# CW313_Power_Supplies.net
KiCad netlist of a schematic drawn in Altium Designer
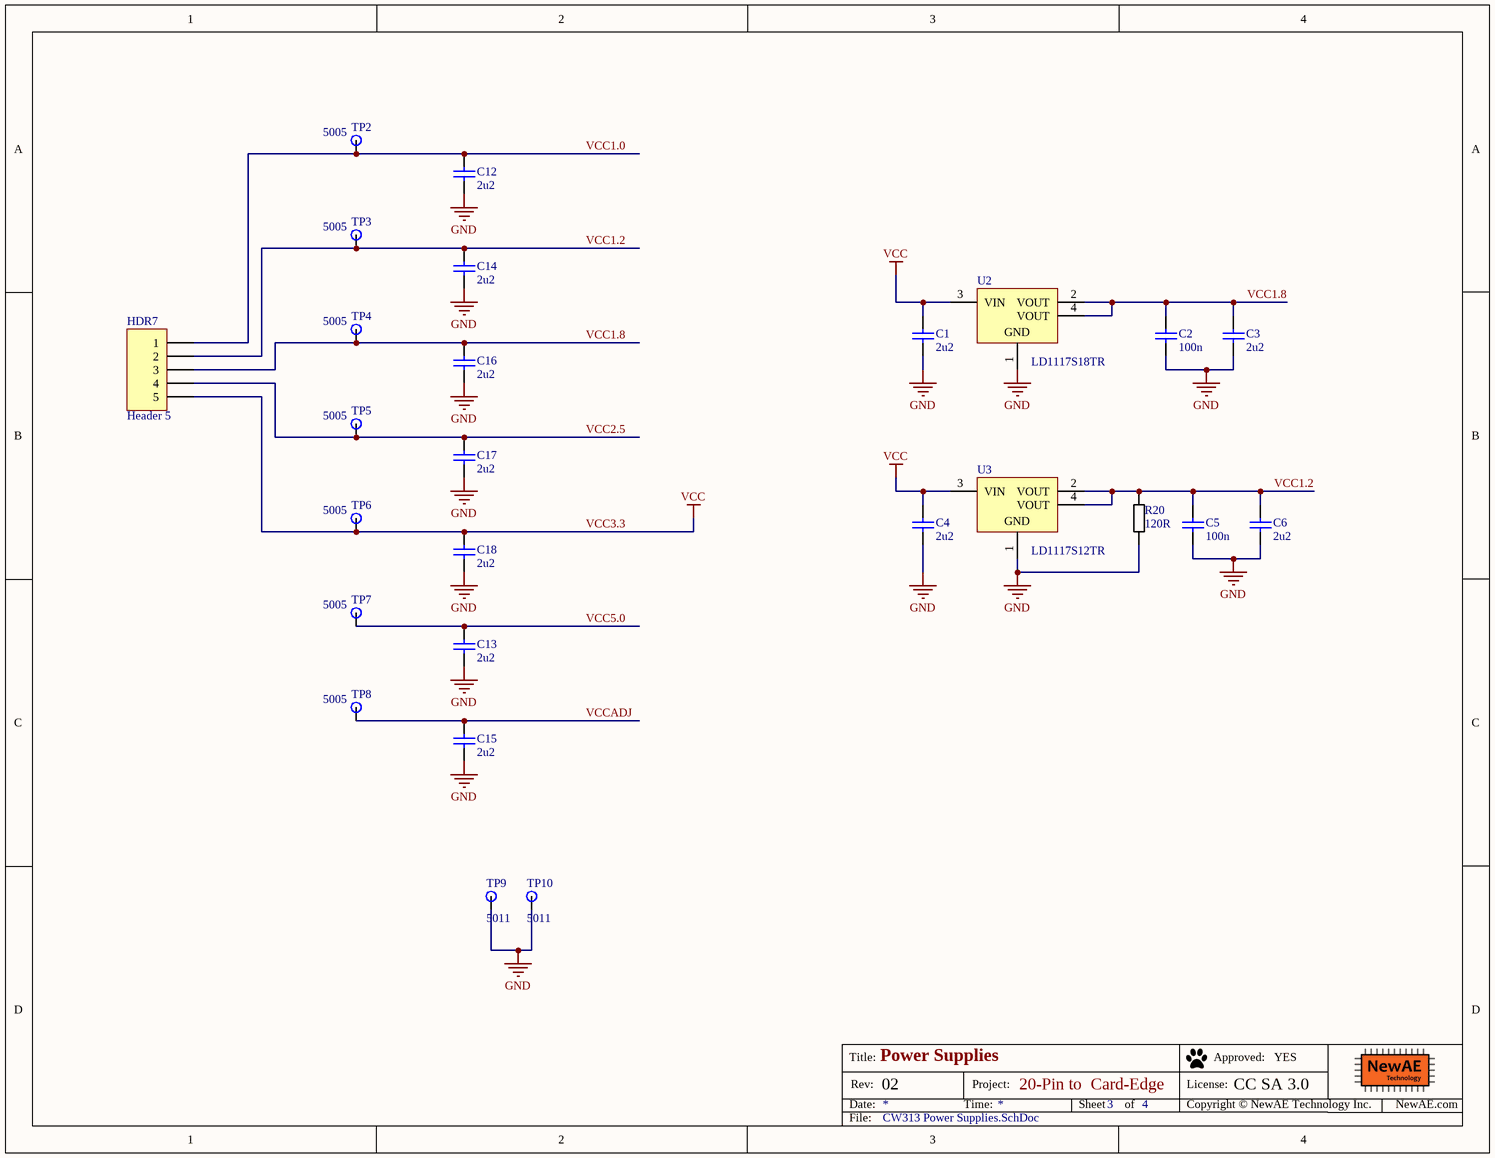
[diagram p0: CW313 Power Supplies.SchDoc]

(export (version "E")
  (design (tool "Eeschema 10.0.6"))
  (components
    (comp (ref "C1")
      (value "2u2")
      (footprint "CAPC0603_M")
      (description "2u2, 0603")
      (fields (field (name "PART NUMBER") "CCHIP-2u2-0603-16V"))
      (libsource (lib "NewAE_AltiumLib") (part "CAP"))
    )
    (comp (ref "C2")
      (value "100n")
      (footprint "CAPC0603_M")
      (description "100n, 0603")
      (fields (field (name "PART NUMBER") "CCHIP-100n-0603"))
      (libsource (lib "NewAE_AltiumLib") (part "CAP"))
    )
    (comp (ref "C3")
      (value "2u2")
      (footprint "CAPC0603_M")
      (description "2u2, 0603")
      (fields (field (name "PART NUMBER") "CCHIP-2u2-0603-16V"))
      (libsource (lib "NewAE_AltiumLib") (part "CAP"))
    )
    (comp (ref "C4")
      (value "2u2")
      (footprint "CAPC0603_M")
      (description "2u2, 0603")
      (fields (field (name "PART NUMBER") "CCHIP-2u2-0603-16V"))
      (libsource (lib "NewAE_AltiumLib") (part "CAP"))
    )
    (comp (ref "C5")
      (value "100n")
      (footprint "CAPC0603_M")
      (description "100n, 0603")
      (fields (field (name "PART NUMBER") "CCHIP-100n-0603"))
      (libsource (lib "NewAE_AltiumLib") (part "CAP"))
    )
    (comp (ref "C6")
      (value "2u2")
      (footprint "CAPC0603_M")
      (description "2u2, 0603")
      (fields (field (name "PART NUMBER") "CCHIP-2u2-0603-16V"))
      (libsource (lib "NewAE_AltiumLib") (part "CAP"))
    )
    (comp (ref "C12")
      (value "2u2")
      (footprint "CAPC0603_M")
      (description "2u2, 0603")
      (fields (field (name "PART NUMBER") "CCHIP-2u2-0603-16V"))
      (libsource (lib "NewAE_AltiumLib") (part "CAP"))
    )
    (comp (ref "C13")
      (value "2u2")
      (footprint "CAPC0603_M")
      (description "2u2, 0603")
      (fields (field (name "PART NUMBER") "CCHIP-2u2-0603-16V"))
      (libsource (lib "NewAE_AltiumLib") (part "CAP"))
    )
    (comp (ref "C14")
      (value "2u2")
      (footprint "CAPC0603_M")
      (description "2u2, 0603")
      (fields (field (name "PART NUMBER") "CCHIP-2u2-0603-16V"))
      (libsource (lib "NewAE_AltiumLib") (part "CAP"))
    )
    (comp (ref "C15")
      (value "2u2")
      (footprint "CAPC0603_M")
      (description "2u2, 0603")
      (fields (field (name "PART NUMBER") "CCHIP-2u2-0603-16V"))
      (libsource (lib "NewAE_AltiumLib") (part "CAP"))
    )
    (comp (ref "C16")
      (value "2u2")
      (footprint "CAPC0603_M")
      (description "2u2, 0603")
      (fields (field (name "PART NUMBER") "CCHIP-2u2-0603-16V"))
      (libsource (lib "NewAE_AltiumLib") (part "CAP"))
    )
    (comp (ref "C17")
      (value "2u2")
      (footprint "CAPC0603_M")
      (description "2u2, 0603")
      (fields (field (name "PART NUMBER") "CCHIP-2u2-0603-16V"))
      (libsource (lib "NewAE_AltiumLib") (part "CAP"))
    )
    (comp (ref "C18")
      (value "2u2")
      (footprint "CAPC0603_M")
      (description "2u2, 0603")
      (fields (field (name "PART NUMBER") "CCHIP-2u2-0603-16V"))
      (libsource (lib "NewAE_AltiumLib") (part "CAP"))
    )
    (comp (ref "HDR7")
      (value "Header 5")
      (footprint "HDR1X5")
      (description "Header, 5-Pin")
      (fields (field (name "PUBLISHER") "Altium Limited"))
      (libsource (lib "Miscellaneous Connectors") (part "Header 5"))
    )
    (comp (ref "R20")
      (value "120R")
      (footprint "RESC1608X55N")
      (description "120R res, 0603, 1%, 1/10W")
      (fields (field (name "PART NUMBER") "RCHIP-120R-0603") (field (name "TOLERANCE") "1%"))
      (libsource (lib "NewAE_AltiumLib") (part "RES-EU"))
    )
    (comp (ref "TP2")
      (value "5005")
      (footprint "KEYSTONE5008")
      (description "TEST POINT PC COMPACT .063\"D RED")
      (fields (field (name "PART NUMBER") "KEYSTONE_5005"))
      (libsource (lib "NewAE_AltiumLib") (part "KEYSTONE_5008"))
    )
    (comp (ref "TP3")
      (value "5005")
      (footprint "KEYSTONE5008")
      (description "TEST POINT PC COMPACT .063\"D RED")
      (fields (field (name "PART NUMBER") "KEYSTONE_5005"))
      (libsource (lib "NewAE_AltiumLib") (part "KEYSTONE_5008"))
    )
    (comp (ref "TP4")
      (value "5005")
      (footprint "KEYSTONE5008")
      (description "TEST POINT PC COMPACT .063\"D RED")
      (fields (field (name "PART NUMBER") "KEYSTONE_5005"))
      (libsource (lib "NewAE_AltiumLib") (part "KEYSTONE_5008"))
    )
    (comp (ref "TP5")
      (value "5005")
      (footprint "KEYSTONE5008")
      (description "TEST POINT PC COMPACT .063\"D RED")
      (fields (field (name "PART NUMBER") "KEYSTONE_5005"))
      (libsource (lib "NewAE_AltiumLib") (part "KEYSTONE_5008"))
    )
    (comp (ref "TP6")
      (value "5005")
      (footprint "KEYSTONE5008")
      (description "TEST POINT PC COMPACT .063\"D RED")
      (fields (field (name "PART NUMBER") "KEYSTONE_5005"))
      (libsource (lib "NewAE_AltiumLib") (part "KEYSTONE_5008"))
    )
    (comp (ref "TP7")
      (value "5005")
      (footprint "KEYSTONE5008")
      (description "TEST POINT PC COMPACT .063\"D RED")
      (fields (field (name "PART NUMBER") "KEYSTONE_5005"))
      (libsource (lib "NewAE_AltiumLib") (part "KEYSTONE_5008"))
    )
    (comp (ref "TP8")
      (value "5005")
      (footprint "KEYSTONE5008")
      (description "TEST POINT PC COMPACT .063\"D RED")
      (fields (field (name "PART NUMBER") "KEYSTONE_5005"))
      (libsource (lib "NewAE_AltiumLib") (part "KEYSTONE_5008"))
    )
    (comp (ref "TP9")
      (value "5011")
      (footprint "KEYSTONE5011")
      (description "TEST POINT PC MULTI PURPOSE BLK")
      (fields (field (name "PART NUMBER") "KEYSTONE_5011"))
      (libsource (lib "NewAE_AltiumLib") (part "KEYSTONE_5011"))
    )
    (comp (ref "TP10")
      (value "5011")
      (footprint "KEYSTONE5011")
      (description "TEST POINT PC MULTI PURPOSE BLK")
      (fields (field (name "PART NUMBER") "KEYSTONE_5011"))
      (libsource (lib "NewAE_AltiumLib") (part "KEYSTONE_5011"))
    )
    (comp (ref "U2")
      (value "LD1117S18TR")
      (footprint "SOT-223_M")
      (description "Fixed Low Drop Positive Voltage Regulator, 1.8V, 4-Pin SOT-223, Tape and Reel")
      (libsource (lib "Altium Content Vault") (part "CMP-0244-00308-1"))
    )
    (comp (ref "U3")
      (value "LD1117S12TR")
      (footprint "SOT-223_M")
      (description "Fixed Low Drop Positive Voltage Regulator, 1.2V, 4-Pin SOT-223, Tape and Reel")
      (libsource (lib "Altium Content Vault") (part "PM-REG-LD1117-SOT4"))
    )
  )
  (nets
    (net (code "1") (name "/VCC1.0") (class "Default")
      (node (ref "C12") (pin "1") (pinfunction "1_1") (pintype "passive"))
      (node (ref "HDR7") (pin "1") (pinfunction "1_1") (pintype "passive"))
      (node (ref "TP2") (pin "1") (pinfunction "1_1") (pintype "passive"))
    )
    (net (code "2") (name "/VCC1.2") (class "Default")
      (node (ref "C14") (pin "1") (pinfunction "1_1") (pintype "passive"))
      (node (ref "C5") (pin "1") (pinfunction "1_1") (pintype "passive"))
      (node (ref "C6") (pin "1") (pinfunction "1_1") (pintype "passive"))
      (node (ref "HDR7") (pin "2") (pinfunction "2_2") (pintype "passive"))
      (node (ref "R20") (pin "1") (pinfunction "1_1") (pintype "passive"))
      (node (ref "TP3") (pin "1") (pinfunction "1_1") (pintype "passive"))
      (node (ref "U3") (pin "2") (pinfunction "VOUT_2") (pintype "power_in"))
      (node (ref "U3") (pin "4") (pinfunction "VOUT_4") (pintype "power_in"))
    )
    (net (code "3") (name "/VCC1.8") (class "Default")
      (node (ref "C16") (pin "1") (pinfunction "1_1") (pintype "passive"))
      (node (ref "C2") (pin "1") (pinfunction "1_1") (pintype "passive"))
      (node (ref "C3") (pin "1") (pinfunction "1_1") (pintype "passive"))
      (node (ref "HDR7") (pin "3") (pinfunction "3_3") (pintype "passive"))
      (node (ref "TP4") (pin "1") (pinfunction "1_1") (pintype "passive"))
      (node (ref "U2") (pin "2") (pinfunction "VOUT_2") (pintype "power_in"))
      (node (ref "U2") (pin "4") (pinfunction "VOUT_4") (pintype "power_in"))
    )
    (net (code "4") (name "/VCC2.5") (class "Default")
      (node (ref "C17") (pin "1") (pinfunction "1_1") (pintype "passive"))
      (node (ref "HDR7") (pin "4") (pinfunction "4_4") (pintype "passive"))
      (node (ref "TP5") (pin "1") (pinfunction "1_1") (pintype "passive"))
    )
    (net (code "5") (name "/VCC5.0") (class "Default")
      (node (ref "C13") (pin "1") (pinfunction "1_1") (pintype "passive"))
      (node (ref "TP7") (pin "1") (pinfunction "1_1") (pintype "passive"))
    )
    (net (code "6") (name "/VCCADJ") (class "Default")
      (node (ref "C15") (pin "1") (pinfunction "1_1") (pintype "passive"))
      (node (ref "TP8") (pin "1") (pinfunction "1_1") (pintype "passive"))
    )
    (net (code "7") (name "GND") (class "Default")
      (node (ref "C1") (pin "2") (pinfunction "2_2") (pintype "passive"))
      (node (ref "C12") (pin "2") (pinfunction "2_2") (pintype "passive"))
      (node (ref "C13") (pin "2") (pinfunction "2_2") (pintype "passive"))
      (node (ref "C14") (pin "2") (pinfunction "2_2") (pintype "passive"))
      (node (ref "C15") (pin "2") (pinfunction "2_2") (pintype "passive"))
      (node (ref "C16") (pin "2") (pinfunction "2_2") (pintype "passive"))
      (node (ref "C17") (pin "2") (pinfunction "2_2") (pintype "passive"))
      (node (ref "C18") (pin "2") (pinfunction "2_2") (pintype "passive"))
      (node (ref "C2") (pin "2") (pinfunction "2_2") (pintype "passive"))
      (node (ref "C3") (pin "2") (pinfunction "2_2") (pintype "passive"))
      (node (ref "C4") (pin "2") (pinfunction "2_2") (pintype "passive"))
      (node (ref "C5") (pin "2") (pinfunction "2_2") (pintype "passive"))
      (node (ref "C6") (pin "2") (pinfunction "2_2") (pintype "passive"))
      (node (ref "R20") (pin "2") (pinfunction "2_2") (pintype "passive"))
      (node (ref "TP10") (pin "1") (pinfunction "1_1") (pintype "passive"))
      (node (ref "TP9") (pin "1") (pinfunction "1_1") (pintype "passive"))
      (node (ref "U2") (pin "1") (pinfunction "GND_1") (pintype "power_in"))
      (node (ref "U3") (pin "1") (pinfunction "GND_1") (pintype "power_in"))
    )
    (net (code "8") (name "VCC") (class "Default")
      (node (ref "C1") (pin "1") (pinfunction "1_1") (pintype "passive"))
      (node (ref "C18") (pin "1") (pinfunction "1_1") (pintype "passive"))
      (node (ref "C4") (pin "1") (pinfunction "1_1") (pintype "passive"))
      (node (ref "HDR7") (pin "5") (pinfunction "5_5") (pintype "passive"))
      (node (ref "TP6") (pin "1") (pinfunction "1_1") (pintype "passive"))
      (node (ref "U2") (pin "3") (pinfunction "VIN_3") (pintype "power_in"))
      (node (ref "U3") (pin "3") (pinfunction "VIN_3") (pintype "power_in"))
    )
  )
)
